# ESP-Easy_FHEM_Multi.net
KiCad netlist of a schematic drawn in EAGLE
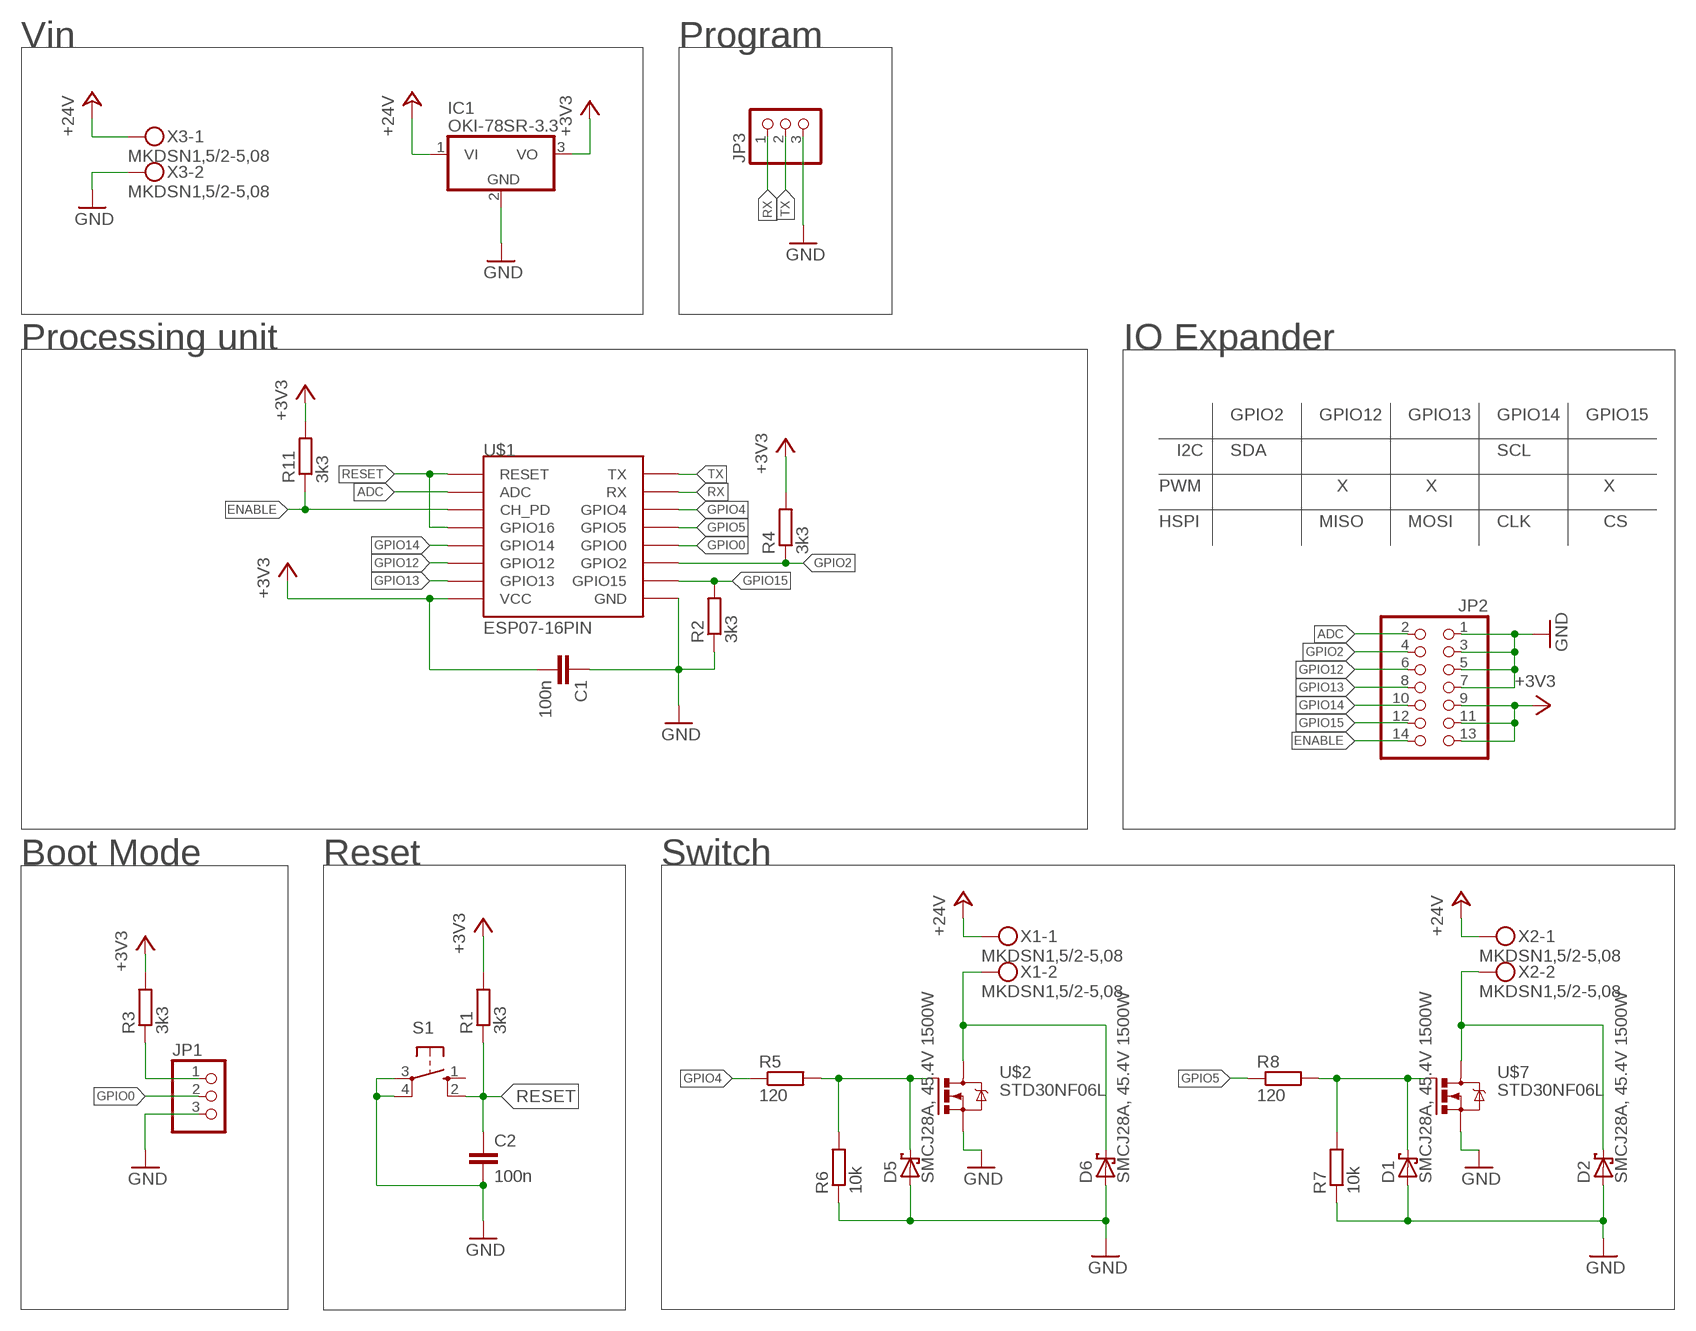
[diagram p0: schematic, sheet 1]

(export (version "E")
  (design (tool "Eeschema 10.0.6"))
  (components
    (comp (ref "C1")
      (value "100n")
      (footprint "eagle-import:C0603")
      (libsource (lib "eagle-import") (part "C-EUC0603"))
    )
    (comp (ref "C2")
      (value "100n")
      (footprint "eagle-import:C0603")
      (libsource (lib "eagle-import") (part "C-EUC0603"))
    )
    (comp (ref "D1")
      (value "SMCJ28A, 45.4V 1500W")
      (footprint "eagle-import:SMC")
      (libsource (lib "eagle-import") (part "SCHOTTKY-DIODESMC"))
    )
    (comp (ref "D2")
      (value "SMCJ28A, 45.4V 1500W")
      (footprint "eagle-import:SMC")
      (libsource (lib "eagle-import") (part "SCHOTTKY-DIODESMC"))
    )
    (comp (ref "D5")
      (value "SMCJ28A, 45.4V 1500W")
      (footprint "eagle-import:SMC")
      (libsource (lib "eagle-import") (part "SCHOTTKY-DIODESMC"))
    )
    (comp (ref "D6")
      (value "SMCJ28A, 45.4V 1500W")
      (footprint "eagle-import:SMC")
      (libsource (lib "eagle-import") (part "SCHOTTKY-DIODESMC"))
    )
    (comp (ref "IC1")
      (value "OKI-78SR-3.3")
      (footprint "eagle-import:TO220V")
      (libsource (lib "eagle-import") (part "78TV05"))
    )
    (comp (ref "JP1")
      (value "PINHD-1X3")
      (footprint "eagle-import:1X03")
      (libsource (lib "eagle-import") (part "PINHD-1X3"))
    )
    (comp (ref "JP2")
      (value "PINHD-2X7")
      (footprint "eagle-import:2X07")
      (libsource (lib "eagle-import") (part "PINHD-2X7"))
    )
    (comp (ref "JP3")
      (value "PINHD-1X3")
      (footprint "eagle-import:1X03")
      (libsource (lib "eagle-import") (part "PINHD-1X3"))
    )
    (comp (ref "R1")
      (value "3k3")
      (footprint "eagle-import:R0603")
      (libsource (lib "eagle-import") (part "R-EU_R0603"))
    )
    (comp (ref "R2")
      (value "3k3")
      (footprint "eagle-import:R0603")
      (libsource (lib "eagle-import") (part "R-EU_R0603"))
    )
    (comp (ref "R3")
      (value "3k3")
      (footprint "eagle-import:R0603")
      (libsource (lib "eagle-import") (part "R-EU_R0603"))
    )
    (comp (ref "R4")
      (value "3k3")
      (footprint "eagle-import:R0603")
      (libsource (lib "eagle-import") (part "R-EU_R0603"))
    )
    (comp (ref "R5")
      (value "120")
      (footprint "eagle-import:R0603")
      (libsource (lib "eagle-import") (part "R-EU_R0603"))
    )
    (comp (ref "R6")
      (value "10k")
      (footprint "eagle-import:R0603")
      (libsource (lib "eagle-import") (part "resistor_348_R-EU_R0603"))
    )
    (comp (ref "R7")
      (value "10k")
      (footprint "eagle-import:R0603")
      (libsource (lib "eagle-import") (part "resistor_348_R-EU_R0603"))
    )
    (comp (ref "R8")
      (value "120")
      (footprint "eagle-import:R0603")
      (libsource (lib "eagle-import") (part "R-EU_R0603"))
    )
    (comp (ref "R11")
      (value "3k3")
      (footprint "eagle-import:R0603")
      (libsource (lib "eagle-import") (part "R-EU_R0603"))
    )
    (comp (ref "S1")
      (value "10-XX")
      (footprint "eagle-import:B3F-10XX")
      (fields (field (name "MPN") "B3F-1000"))
      (libsource (lib "eagle-import") (part "10-XX"))
    )
    (comp (ref "U$1")
      (value "ESP07-16PIN")
      (footprint "eagle-import:ESP07-16PIN")
      (libsource (lib "eagle-import") (part "ESP07-16PIN"))
    )
    (comp (ref "U$2")
      (value "STD30NF06L")
      (footprint "eagle-import:D-PAK_TO252AA")
      (libsource (lib "eagle-import") (part "STD30NF06L"))
    )
    (comp (ref "U$7")
      (value "STD30NF06L")
      (footprint "eagle-import:D-PAK_TO252AA")
      (libsource (lib "eagle-import") (part "STD30NF06L"))
    )
    (comp (ref "X1")
      (value "MKDSN1,5/2-5,08")
      (footprint "eagle-import:MKDSN1,5_2-5,08")
      (libsource (lib "eagle-import") (part "MKDSN1,5/2-5,08"))
    )
    (comp (ref "X2")
      (value "MKDSN1,5/2-5,08")
      (footprint "eagle-import:MKDSN1,5_2-5,08")
      (libsource (lib "eagle-import") (part "MKDSN1,5/2-5,08"))
    )
    (comp (ref "X3")
      (value "MKDSN1,5/2-5,08")
      (footprint "eagle-import:MKDSN1,5_2-5,08")
      (libsource (lib "eagle-import") (part "MKDSN1,5/2-5,08"))
    )
  )
  (nets
    (net (code "1") (name "+3V3") (class "Default")
      (node (ref "C1") (pin "2") (pinfunction "2_2") (pintype "passive"))
      (node (ref "IC1") (pin "3") (pinfunction "VO_3") (pintype "passive"))
      (node (ref "JP2") (pin "11") (pinfunction "11_11") (pintype "passive"))
      (node (ref "JP2") (pin "13") (pinfunction "13_13") (pintype "passive"))
      (node (ref "JP2") (pin "9") (pinfunction "9_9") (pintype "passive"))
      (node (ref "R1") (pin "2") (pinfunction "2_2") (pintype "passive"))
      (node (ref "R11") (pin "2") (pinfunction "2_2") (pintype "passive"))
      (node (ref "R3") (pin "2") (pinfunction "2_2") (pintype "passive"))
      (node (ref "R4") (pin "2") (pinfunction "2_2") (pintype "passive"))
      (node (ref "U$1") (pin "VCC") (pinfunction "VCC_VCC") (pintype "bidirectional"))
    )
    (net (code "2") (name "+24V") (class "Default")
      (node (ref "IC1") (pin "1") (pinfunction "VI_1") (pintype "input"))
      (node (ref "X1") (pin "1") (pinfunction "KL_1") (pintype "passive"))
      (node (ref "X2") (pin "1") (pinfunction "KL_1") (pintype "passive"))
      (node (ref "X3") (pin "1") (pinfunction "KL_1") (pintype "passive"))
    )
    (net (code "3") (name "ADC") (class "Default")
      (node (ref "JP2") (pin "2") (pinfunction "2_2") (pintype "passive"))
      (node (ref "U$1") (pin "ADC") (pinfunction "ADC_ADC") (pintype "bidirectional"))
    )
    (net (code "4") (name "ENABLE") (class "Default")
      (node (ref "JP2") (pin "14") (pinfunction "14_14") (pintype "passive"))
      (node (ref "R11") (pin "1") (pinfunction "1_1") (pintype "passive"))
      (node (ref "U$1") (pin "CH_PD") (pinfunction "CH_PD_CH_PD") (pintype "bidirectional"))
    )
    (net (code "5") (name "GND") (class "Default")
      (node (ref "C1") (pin "1") (pinfunction "1_1") (pintype "passive"))
      (node (ref "C2") (pin "2") (pinfunction "2_2") (pintype "passive"))
      (node (ref "D1") (pin "A") (pinfunction "A_A") (pintype "passive"))
      (node (ref "D2") (pin "A") (pinfunction "A_A") (pintype "passive"))
      (node (ref "D5") (pin "A") (pinfunction "A_A") (pintype "passive"))
      (node (ref "D6") (pin "A") (pinfunction "A_A") (pintype "passive"))
      (node (ref "IC1") (pin "2") (pinfunction "GND_2") (pintype "passive"))
      (node (ref "JP1") (pin "3") (pinfunction "3_3") (pintype "passive"))
      (node (ref "JP2") (pin "1") (pinfunction "1_1") (pintype "passive"))
      (node (ref "JP2") (pin "3") (pinfunction "3_3") (pintype "passive"))
      (node (ref "JP2") (pin "5") (pinfunction "5_5") (pintype "passive"))
      (node (ref "JP2") (pin "7") (pinfunction "7_7") (pintype "passive"))
      (node (ref "JP3") (pin "3") (pinfunction "3_3") (pintype "passive"))
      (node (ref "R2") (pin "1") (pinfunction "1_1") (pintype "passive"))
      (node (ref "R6") (pin "1") (pinfunction "1_1") (pintype "passive"))
      (node (ref "R7") (pin "1") (pinfunction "1_1") (pintype "passive"))
      (node (ref "S1") (pin "3") (pinfunction "P_3") (pintype "passive"))
      (node (ref "S1") (pin "4") (pinfunction "P1_4") (pintype "passive"))
      (node (ref "U$1") (pin "GND") (pinfunction "GND_GND") (pintype "bidirectional"))
      (node (ref "U$2") (pin "3") (pinfunction "S_3") (pintype "passive"))
      (node (ref "U$7") (pin "3") (pinfunction "S_3") (pintype "passive"))
      (node (ref "X3") (pin "2") (pinfunction "KL_2") (pintype "passive"))
    )
    (net (code "6") (name "GPIO0") (class "Default")
      (node (ref "JP1") (pin "2") (pinfunction "2_2") (pintype "passive"))
      (node (ref "U$1") (pin "GPIO0") (pinfunction "GPIO0_GPIO0") (pintype "bidirectional"))
    )
    (net (code "7") (name "GPIO2") (class "Default")
      (node (ref "JP2") (pin "4") (pinfunction "4_4") (pintype "passive"))
      (node (ref "R4") (pin "1") (pinfunction "1_1") (pintype "passive"))
      (node (ref "U$1") (pin "GPIO2") (pinfunction "GPIO2_GPIO2") (pintype "bidirectional"))
    )
    (net (code "8") (name "GPIO4") (class "Default")
      (node (ref "R5") (pin "1") (pinfunction "1_1") (pintype "passive"))
      (node (ref "U$1") (pin "GPIO4") (pinfunction "GPIO4_GPIO4") (pintype "bidirectional"))
    )
    (net (code "9") (name "GPIO5") (class "Default")
      (node (ref "R8") (pin "1") (pinfunction "1_1") (pintype "passive"))
      (node (ref "U$1") (pin "GPIO5") (pinfunction "GPIO5_GPIO5") (pintype "bidirectional"))
    )
    (net (code "10") (name "GPIO12") (class "Default")
      (node (ref "JP2") (pin "6") (pinfunction "6_6") (pintype "passive"))
      (node (ref "U$1") (pin "GPIO12") (pinfunction "GPIO12_GPIO12") (pintype "bidirectional"))
    )
    (net (code "11") (name "GPIO13") (class "Default")
      (node (ref "JP2") (pin "8") (pinfunction "8_8") (pintype "passive"))
      (node (ref "U$1") (pin "GPIO13") (pinfunction "GPIO13_GPIO13") (pintype "bidirectional"))
    )
    (net (code "12") (name "GPIO14") (class "Default")
      (node (ref "JP2") (pin "10") (pinfunction "10_10") (pintype "passive"))
      (node (ref "U$1") (pin "GPIO14") (pinfunction "GPIO14_GPIO14") (pintype "bidirectional"))
    )
    (net (code "13") (name "GPIO15") (class "Default")
      (node (ref "JP2") (pin "12") (pinfunction "12_12") (pintype "passive"))
      (node (ref "R2") (pin "2") (pinfunction "2_2") (pintype "passive"))
      (node (ref "U$1") (pin "GPIO15") (pinfunction "GPIO15_GPIO15") (pintype "bidirectional"))
    )
    (net (code "14") (name "Net-(JP1-Pad1)") (class "Default")
      (node (ref "JP1") (pin "1") (pinfunction "1_1") (pintype "passive"))
      (node (ref "R3") (pin "1") (pinfunction "1_1") (pintype "passive"))
    )
    (net (code "15") (name "Net-(U$2-D)") (class "Default")
      (node (ref "D6") (pin "C") (pinfunction "C_C") (pintype "passive"))
      (node (ref "U$2") (pin "4") (pinfunction "D_4") (pintype "passive"))
      (node (ref "X1") (pin "2") (pinfunction "KL_2") (pintype "passive"))
    )
    (net (code "16") (name "Net-(U$2-G)") (class "Default")
      (node (ref "D5") (pin "C") (pinfunction "C_C") (pintype "passive"))
      (node (ref "R5") (pin "2") (pinfunction "2_2") (pintype "passive"))
      (node (ref "R6") (pin "2") (pinfunction "2_2") (pintype "passive"))
      (node (ref "U$2") (pin "1") (pinfunction "G_1") (pintype "passive"))
    )
    (net (code "17") (name "Net-(U$7-D)") (class "Default")
      (node (ref "D2") (pin "C") (pinfunction "C_C") (pintype "passive"))
      (node (ref "U$7") (pin "4") (pinfunction "D_4") (pintype "passive"))
      (node (ref "X2") (pin "2") (pinfunction "KL_2") (pintype "passive"))
    )
    (net (code "18") (name "Net-(U$7-G)") (class "Default")
      (node (ref "D1") (pin "C") (pinfunction "C_C") (pintype "passive"))
      (node (ref "R7") (pin "2") (pinfunction "2_2") (pintype "passive"))
      (node (ref "R8") (pin "2") (pinfunction "2_2") (pintype "passive"))
      (node (ref "U$7") (pin "1") (pinfunction "G_1") (pintype "passive"))
    )
    (net (code "19") (name "RESET") (class "Default")
      (node (ref "C2") (pin "1") (pinfunction "1_1") (pintype "passive"))
      (node (ref "R1") (pin "1") (pinfunction "1_1") (pintype "passive"))
      (node (ref "S1") (pin "2") (pinfunction "S1_2") (pintype "passive"))
      (node (ref "U$1") (pin "GPIO16") (pinfunction "GPIO16_GPIO16") (pintype "bidirectional"))
      (node (ref "U$1") (pin "REST") (pinfunction "RESET_REST") (pintype "bidirectional"))
    )
    (net (code "20") (name "RX") (class "Default")
      (node (ref "JP3") (pin "1") (pinfunction "1_1") (pintype "passive"))
      (node (ref "U$1") (pin "RX") (pinfunction "RX_RX") (pintype "bidirectional"))
    )
    (net (code "21") (name "TX") (class "Default")
      (node (ref "JP3") (pin "2") (pinfunction "2_2") (pintype "passive"))
      (node (ref "U$1") (pin "TX") (pinfunction "TX_TX") (pintype "bidirectional"))
    )
    (net (code "22") (name "unconnected-(S1-S-Pad1)") (class "Default")
      (node (ref "S1") (pin "1") (pinfunction "S_1") (pintype "passive"))
    )
  )
)
